# Usb_C_Hub-EasyEdaPro_Project.net
KiCad netlist of a schematic drawn in EasyEDA Pro
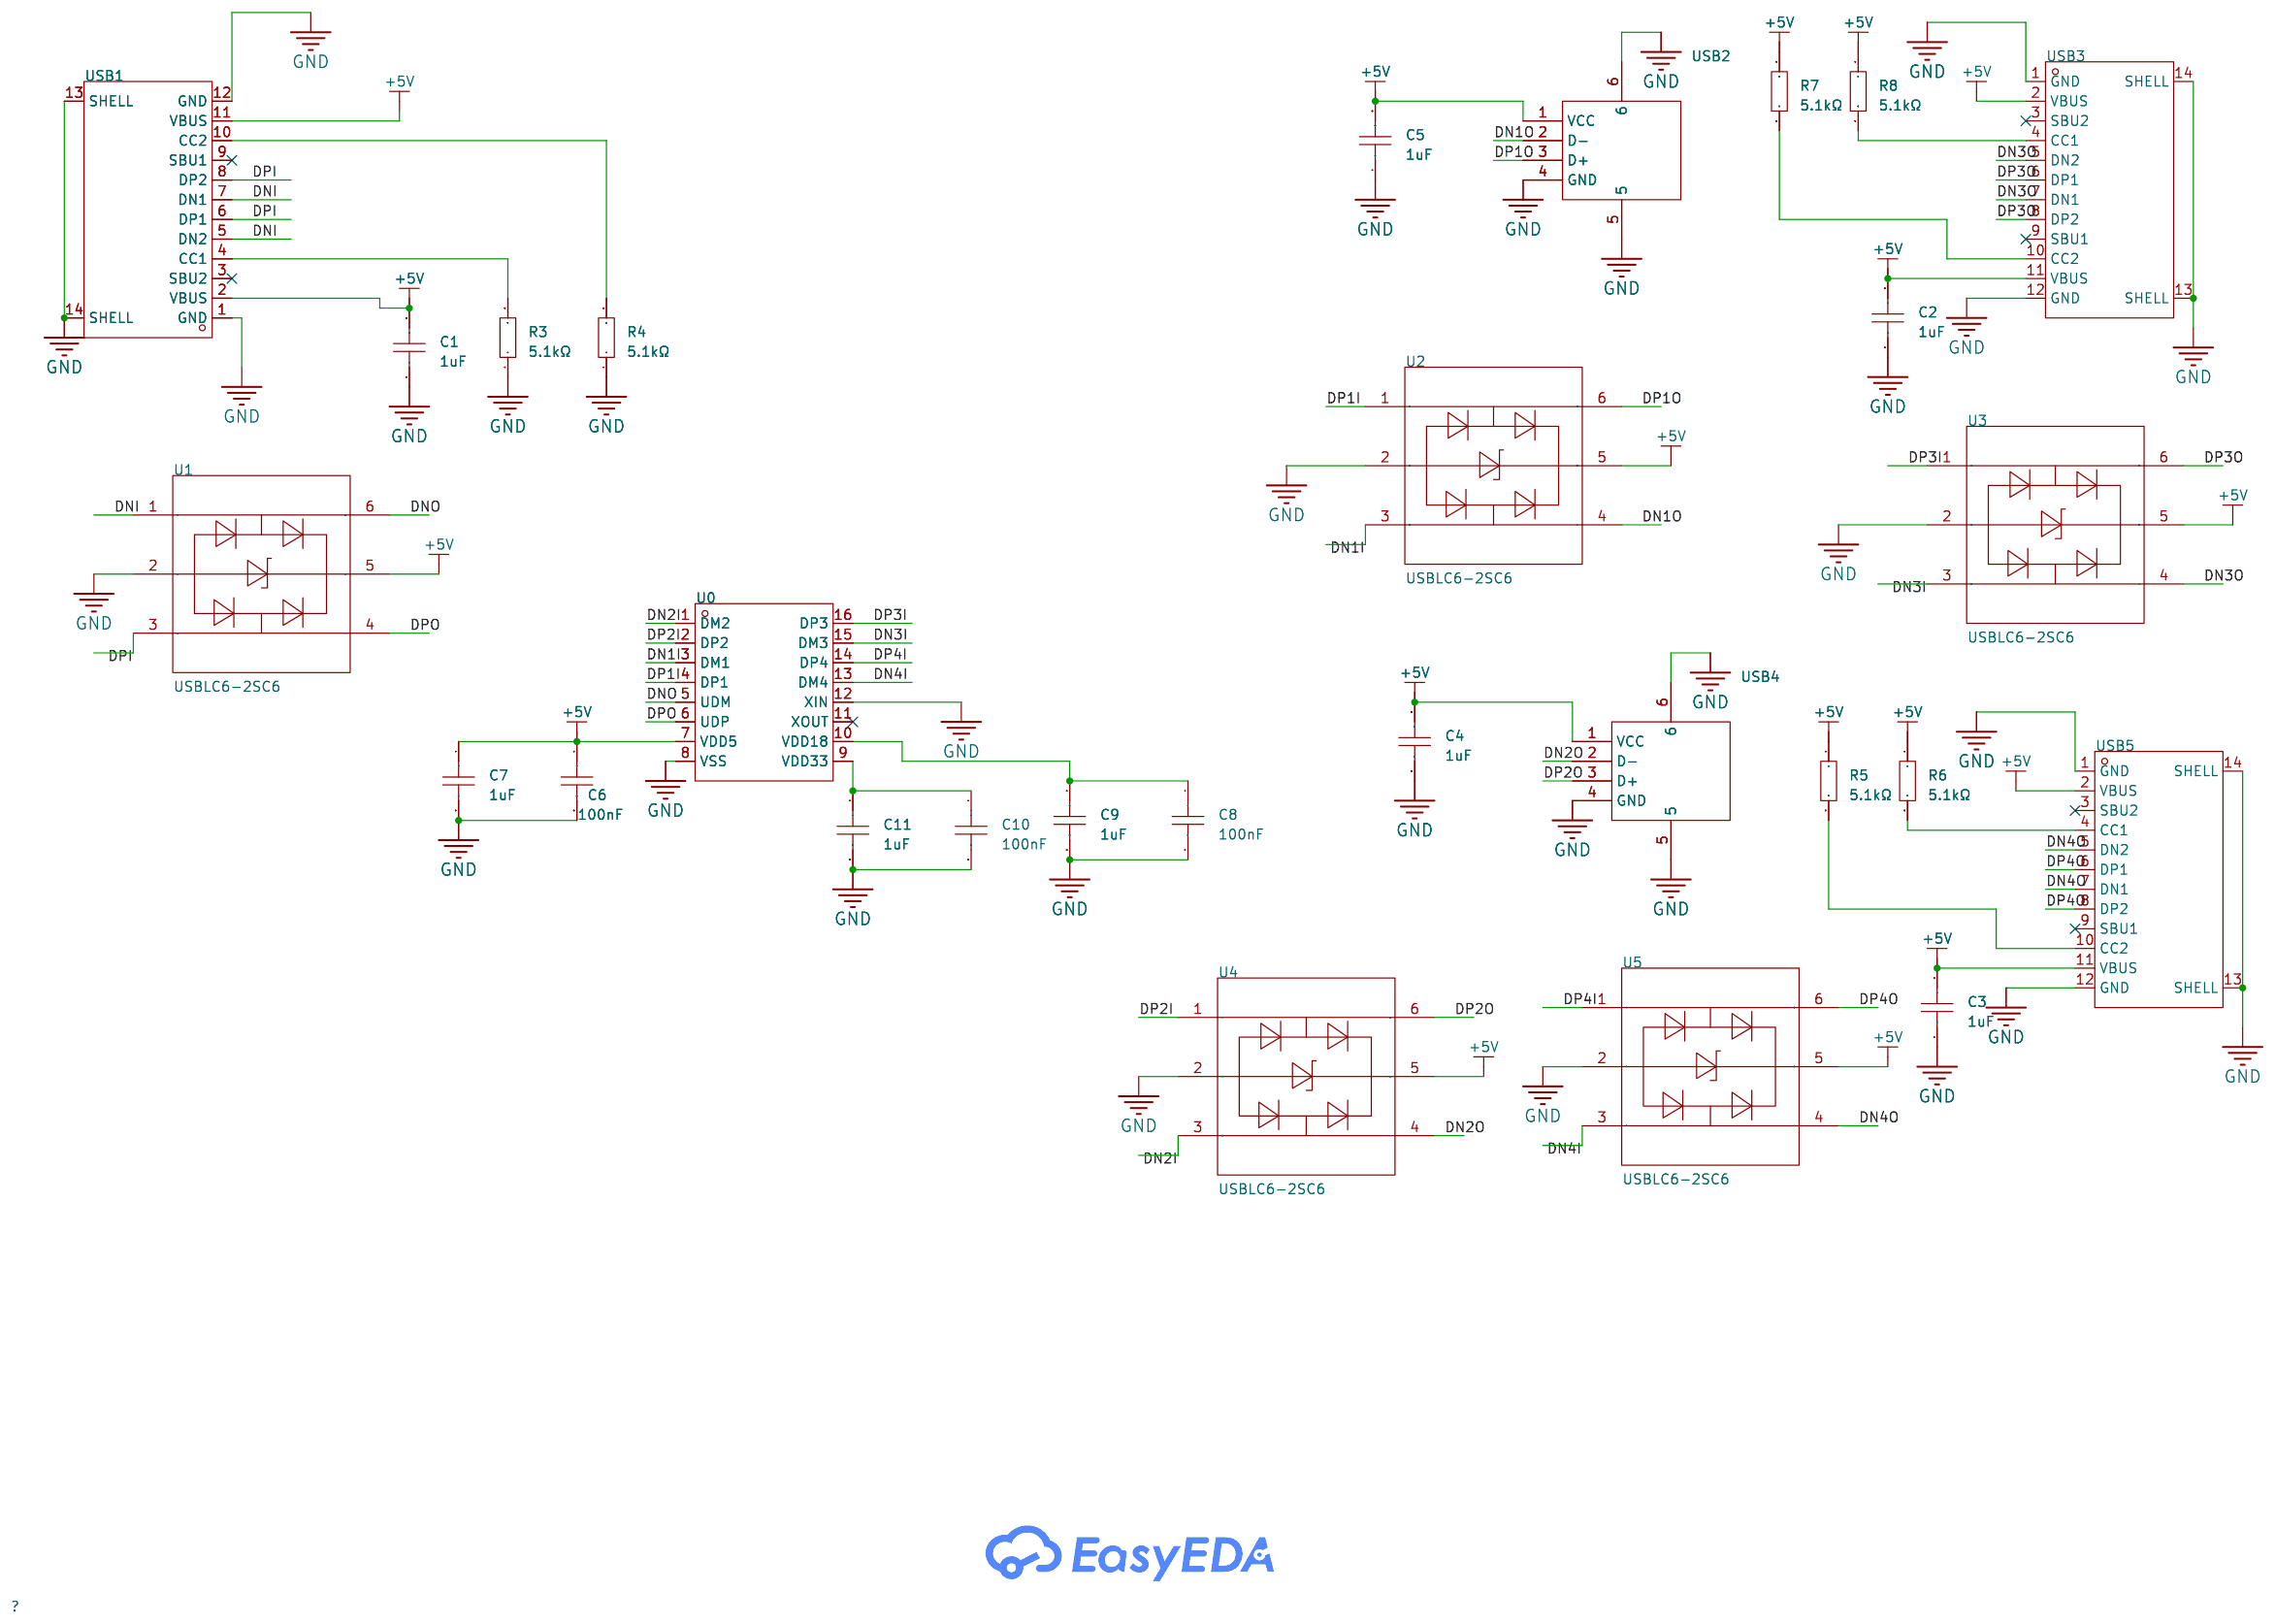
[diagram p0: schematic sheet]

(export (version "E")
  (design (tool "Eeschema 10.0.6"))
  (components
    (comp (ref "C1")
      (value "1uF")
      (footprint "easyedapro:C0603")
      (description "Capacitance:1uF Tolerance:±10% Tolerance:±10% Voltage Rating:50V Temperature Coefficient:X5R")
      (fields
        (field (name "Manufacturer Part") "CL10A105KB8NNNC")
        (field (name "Manufacturer") "SAMSUNG(三星)")
      )
      (libsource (lib "easyedapro") (part "CAP"))
    )
    (comp (ref "C2")
      (value "1uF")
      (footprint "easyedapro:C0603")
      (description "Capacitance:1uF Tolerance:±10% Tolerance:±10% Voltage Rating:50V Temperature Coefficient:X5R")
      (fields
        (field (name "Manufacturer Part") "CL10A105KB8NNNC")
        (field (name "Manufacturer") "SAMSUNG(三星)")
      )
      (libsource (lib "easyedapro") (part "CAP"))
    )
    (comp (ref "C3")
      (value "1uF")
      (footprint "easyedapro:C0603")
      (description "Capacitance:1uF Tolerance:±10% Tolerance:±10% Voltage Rating:50V Temperature Coefficient:X5R")
      (fields
        (field (name "Manufacturer Part") "CL10A105KB8NNNC")
        (field (name "Manufacturer") "SAMSUNG(三星)")
      )
      (libsource (lib "easyedapro") (part "CAP"))
    )
    (comp (ref "C4")
      (value "1uF")
      (footprint "easyedapro:C0603")
      (description "Capacitance:1uF Tolerance:±10% Tolerance:±10% Voltage Rating:50V Temperature Coefficient:X5R")
      (fields
        (field (name "Manufacturer Part") "CL10A105KB8NNNC")
        (field (name "Manufacturer") "SAMSUNG(三星)")
      )
      (libsource (lib "easyedapro") (part "CAP"))
    )
    (comp (ref "C5")
      (value "1uF")
      (footprint "easyedapro:C0603")
      (description "Capacitance:1uF Tolerance:±10% Tolerance:±10% Voltage Rating:50V Temperature Coefficient:X5R")
      (fields
        (field (name "Manufacturer Part") "CL10A105KB8NNNC")
        (field (name "Manufacturer") "SAMSUNG(三星)")
      )
      (libsource (lib "easyedapro") (part "CAP"))
    )
    (comp (ref "C6")
      (value "100nF")
      (footprint "easyedapro:C0603")
      (description "Capacitance:100nF Tolerance:±10% Tolerance:±10% Voltage Rating:50V Temperature Coefficient:X7R")
      (fields
        (field (name "Manufacturer Part") "CC0603KRX7R9BB104")
        (field (name "Manufacturer") "YAGEO(国巨)")
      )
      (libsource (lib "easyedapro") (part "CAP"))
    )
    (comp (ref "C7")
      (value "1uF")
      (footprint "easyedapro:C0603")
      (description "Capacitance:1uF Tolerance:±10% Tolerance:±10% Voltage Rating:50V Temperature Coefficient:X5R")
      (fields
        (field (name "Manufacturer Part") "CL10A105KB8NNNC")
        (field (name "Manufacturer") "SAMSUNG(三星)")
      )
      (libsource (lib "easyedapro") (part "CAP"))
    )
    (comp (ref "C8")
      (value "100nF")
      (footprint "easyedapro:C0603")
      (description "Capacitance:100nF Tolerance:±10% Tolerance:±10% Voltage Rating:50V Temperature Coefficient:X7R")
      (fields
        (field (name "Manufacturer Part") "CC0603KRX7R9BB104")
        (field (name "Manufacturer") "YAGEO(国巨)")
      )
      (libsource (lib "easyedapro") (part "CAP"))
    )
    (comp (ref "C9")
      (value "1uF")
      (footprint "easyedapro:C0603")
      (description "Capacitance:1uF Tolerance:±10% Tolerance:±10% Voltage Rating:50V Temperature Coefficient:X5R")
      (fields
        (field (name "Manufacturer Part") "CL10A105KB8NNNC")
        (field (name "Manufacturer") "SAMSUNG(三星)")
      )
      (libsource (lib "easyedapro") (part "CAP"))
    )
    (comp (ref "C10")
      (value "100nF")
      (footprint "easyedapro:C0603")
      (description "Capacitance:100nF Tolerance:±10% Tolerance:±10% Voltage Rating:50V Temperature Coefficient:X7R")
      (fields
        (field (name "Manufacturer Part") "CC0603KRX7R9BB104")
        (field (name "Manufacturer") "YAGEO(国巨)")
      )
      (libsource (lib "easyedapro") (part "CAP"))
    )
    (comp (ref "C11")
      (value "1uF")
      (footprint "easyedapro:C0603")
      (description "Capacitance:1uF Tolerance:±10% Tolerance:±10% Voltage Rating:50V Temperature Coefficient:X5R")
      (fields
        (field (name "Manufacturer Part") "CL10A105KB8NNNC")
        (field (name "Manufacturer") "SAMSUNG(三星)")
      )
      (libsource (lib "easyedapro") (part "CAP"))
    )
    (comp (ref "R3")
      (value "5.1kΩ")
      (footprint "easyedapro:R0603")
      (fields
        (field (name "Manufacturer Part") "0603WAF5101T5E")
        (field (name "Manufacturer") "UNI-ROYAL(厚声)")
      )
      (libsource (lib "easyedapro") (part "Res"))
    )
    (comp (ref "R4")
      (value "5.1kΩ")
      (footprint "easyedapro:R0603")
      (fields
        (field (name "Manufacturer Part") "0603WAF5101T5E")
        (field (name "Manufacturer") "UNI-ROYAL(厚声)")
      )
      (libsource (lib "easyedapro") (part "Res"))
    )
    (comp (ref "R5")
      (value "5.1kΩ")
      (footprint "easyedapro:R0603")
      (fields
        (field (name "Manufacturer Part") "0603WAF5101T5E")
        (field (name "Manufacturer") "UNI-ROYAL(厚声)")
      )
      (libsource (lib "easyedapro") (part "Res"))
    )
    (comp (ref "R6")
      (value "5.1kΩ")
      (footprint "easyedapro:R0603")
      (fields
        (field (name "Manufacturer Part") "0603WAF5101T5E")
        (field (name "Manufacturer") "UNI-ROYAL(厚声)")
      )
      (libsource (lib "easyedapro") (part "Res"))
    )
    (comp (ref "R7")
      (value "5.1kΩ")
      (footprint "easyedapro:R0603")
      (fields
        (field (name "Manufacturer Part") "0603WAF5101T5E")
        (field (name "Manufacturer") "UNI-ROYAL(厚声)")
      )
      (libsource (lib "easyedapro") (part "Res"))
    )
    (comp (ref "R8")
      (value "5.1kΩ")
      (footprint "easyedapro:R0603")
      (fields
        (field (name "Manufacturer Part") "0603WAF5101T5E")
        (field (name "Manufacturer") "UNI-ROYAL(厚声)")
      )
      (libsource (lib "easyedapro") (part "Res"))
    )
    (comp (ref "U0")
      (value "SL2.1s")
      (footprint "easyedapro:SSOP-16_L4.6-W2.6-P0.53-LS4.0-BL")
      (fields (field (name "Manufacturer") "CoreChips(和芯润德)"))
      (libsource (lib "easyedapro") (part "SL2.1S"))
    )
    (comp (ref "U1")
      (value "USBLC6-2SC6")
      (footprint "easyedapro:SOT-23-6_L2.9-W1.6-P0.95-LS2.8-BR")
      (fields (field (name "Manufacturer") "HXY MOSFET(华轩阳电子)"))
      (libsource (lib "easyedapro") (part "USBLC6-2SC6_C5261088"))
    )
    (comp (ref "U2")
      (value "USBLC6-2SC6")
      (footprint "easyedapro:SOT-23-6_L2.9-W1.6-P0.95-LS2.8-BR")
      (fields (field (name "Manufacturer") "HXY MOSFET(华轩阳电子)"))
      (libsource (lib "easyedapro") (part "USBLC6-2SC6_C5261088"))
    )
    (comp (ref "U3")
      (value "USBLC6-2SC6")
      (footprint "easyedapro:SOT-23-6_L2.9-W1.6-P0.95-LS2.8-BR")
      (fields (field (name "Manufacturer") "HXY MOSFET(华轩阳电子)"))
      (libsource (lib "easyedapro") (part "USBLC6-2SC6_C5261088"))
    )
    (comp (ref "U4")
      (value "USBLC6-2SC6")
      (footprint "easyedapro:SOT-23-6_L2.9-W1.6-P0.95-LS2.8-BR")
      (fields (field (name "Manufacturer") "HXY MOSFET(华轩阳电子)"))
      (libsource (lib "easyedapro") (part "USBLC6-2SC6_C5261088"))
    )
    (comp (ref "U5")
      (value "USBLC6-2SC6")
      (footprint "easyedapro:SOT-23-6_L2.9-W1.6-P0.95-LS2.8-BR")
      (fields (field (name "Manufacturer") "HXY MOSFET(华轩阳电子)"))
      (libsource (lib "easyedapro") (part "USBLC6-2SC6_C5261088"))
    )
    (comp (ref "USB1")
      (value "TYPE-C 16PIN 2MD(073)")
      (footprint "easyedapro:USB-C-SMD_TYPE-C-6PIN-2MD-073")
      (fields (field (name "Manufacturer") "SHOU HAN(首韩)"))
      (libsource (lib "easyedapro") (part "TYPE-C 16PIN 2MD(073)"))
    )
    (comp (ref "USB2")
      (value "10.0 QHHTZB6.3")
      (footprint "easyedapro:USB-A-TH_10.0QHHTZB6.3")
      (fields (field (name "Manufacturer") "SHOU HAN(首韩)"))
      (libsource (lib "easyedapro") (part "10.0 QHHTZB6.3"))
    )
    (comp (ref "USB3")
      (value "TYPE-C 16PIN 2MD(073)")
      (footprint "easyedapro:USB-C-SMD_TYPE-C-6PIN-2MD-073")
      (fields (field (name "Manufacturer") "SHOU HAN(首韩)"))
      (libsource (lib "easyedapro") (part "TYPE-C 16PIN 2MD(073)"))
    )
    (comp (ref "USB4")
      (value "10.0 QHHTZB6.3")
      (footprint "easyedapro:USB-A-TH_10.0QHHTZB6.3")
      (fields (field (name "Manufacturer") "SHOU HAN(首韩)"))
      (libsource (lib "easyedapro") (part "10.0 QHHTZB6.3"))
    )
    (comp (ref "USB5")
      (value "TYPE-C 16PIN 2MD(073)")
      (footprint "easyedapro:USB-C-SMD_TYPE-C-6PIN-2MD-073")
      (fields (field (name "Manufacturer") "SHOU HAN(首韩)"))
      (libsource (lib "easyedapro") (part "TYPE-C 16PIN 2MD(073)"))
    )
  )
  (nets
    (net (code "1") (name "+5V") (class "Default")
      (node (ref "C1") (pin "2") (pinfunction "2_2") (pintype "input"))
      (node (ref "C2") (pin "2") (pinfunction "2_2") (pintype "input"))
      (node (ref "C3") (pin "2") (pinfunction "2_2") (pintype "input"))
      (node (ref "C4") (pin "2") (pinfunction "2_2") (pintype "input"))
      (node (ref "C5") (pin "2") (pinfunction "2_2") (pintype "input"))
      (node (ref "C6") (pin "1") (pinfunction "1_1") (pintype "input"))
      (node (ref "C7") (pin "1") (pinfunction "1_1") (pintype "input"))
      (node (ref "R5") (pin "1") (pinfunction "1_1") (pintype "input"))
      (node (ref "R6") (pin "1") (pinfunction "1_1") (pintype "input"))
      (node (ref "R7") (pin "1") (pinfunction "1_1") (pintype "input"))
      (node (ref "R8") (pin "1") (pinfunction "1_1") (pintype "input"))
      (node (ref "U0") (pin "7") (pinfunction "VDD5_7") (pintype "unspecified"))
      (node (ref "U1") (pin "5") (pinfunction "5_5") (pintype "input"))
      (node (ref "U2") (pin "5") (pinfunction "5_5") (pintype "input"))
      (node (ref "U3") (pin "5") (pinfunction "5_5") (pintype "input"))
      (node (ref "U4") (pin "5") (pinfunction "5_5") (pintype "input"))
      (node (ref "U5") (pin "5") (pinfunction "5_5") (pintype "input"))
      (node (ref "USB1") (pin "11") (pinfunction "VBUS_11") (pintype "unspecified"))
      (node (ref "USB1") (pin "2") (pinfunction "VBUS_2") (pintype "unspecified"))
      (node (ref "USB2") (pin "1") (pinfunction "VCC_1") (pintype "unspecified"))
      (node (ref "USB3") (pin "11") (pinfunction "VBUS_11") (pintype "unspecified"))
      (node (ref "USB3") (pin "2") (pinfunction "VBUS_2") (pintype "unspecified"))
      (node (ref "USB4") (pin "1") (pinfunction "VCC_1") (pintype "unspecified"))
      (node (ref "USB5") (pin "11") (pinfunction "VBUS_11") (pintype "unspecified"))
      (node (ref "USB5") (pin "2") (pinfunction "VBUS_2") (pintype "unspecified"))
    )
    (net (code "2") (name "/DN1I") (class "Default")
      (node (ref "U0") (pin "3") (pinfunction "DM1_3") (pintype "unspecified"))
      (node (ref "U2") (pin "3") (pinfunction "3_3") (pintype "input"))
    )
    (net (code "3") (name "/DN1O") (class "Default")
      (node (ref "U2") (pin "4") (pinfunction "4_4") (pintype "input"))
      (node (ref "USB2") (pin "2") (pinfunction "D-_2") (pintype "unspecified"))
    )
    (net (code "4") (name "/DN2I") (class "Default")
      (node (ref "U0") (pin "1") (pinfunction "DM2_1") (pintype "unspecified"))
      (node (ref "U4") (pin "3") (pinfunction "3_3") (pintype "input"))
    )
    (net (code "5") (name "/DN2O") (class "Default")
      (node (ref "U4") (pin "4") (pinfunction "4_4") (pintype "input"))
      (node (ref "USB4") (pin "2") (pinfunction "D-_2") (pintype "unspecified"))
    )
    (net (code "6") (name "/DN3I") (class "Default")
      (node (ref "U0") (pin "15") (pinfunction "DM3_15") (pintype "unspecified"))
      (node (ref "U3") (pin "3") (pinfunction "3_3") (pintype "input"))
    )
    (net (code "7") (name "/DN3O") (class "Default")
      (node (ref "U3") (pin "4") (pinfunction "4_4") (pintype "input"))
      (node (ref "USB3") (pin "5") (pinfunction "DN2_5") (pintype "unspecified"))
      (node (ref "USB3") (pin "7") (pinfunction "DN1_7") (pintype "unspecified"))
    )
    (net (code "8") (name "/DN4I") (class "Default")
      (node (ref "U0") (pin "13") (pinfunction "DM4_13") (pintype "unspecified"))
      (node (ref "U5") (pin "3") (pinfunction "3_3") (pintype "input"))
    )
    (net (code "9") (name "/DN4O") (class "Default")
      (node (ref "U5") (pin "4") (pinfunction "4_4") (pintype "input"))
      (node (ref "USB5") (pin "5") (pinfunction "DN2_5") (pintype "unspecified"))
      (node (ref "USB5") (pin "7") (pinfunction "DN1_7") (pintype "unspecified"))
    )
    (net (code "10") (name "/DNI") (class "Default")
      (node (ref "U1") (pin "1") (pinfunction "1_1") (pintype "input"))
      (node (ref "USB1") (pin "5") (pinfunction "DN2_5") (pintype "unspecified"))
      (node (ref "USB1") (pin "7") (pinfunction "DN1_7") (pintype "unspecified"))
    )
    (net (code "11") (name "/DNO") (class "Default")
      (node (ref "U0") (pin "5") (pinfunction "UDM_5") (pintype "unspecified"))
      (node (ref "U1") (pin "6") (pinfunction "6_6") (pintype "input"))
    )
    (net (code "12") (name "/DP1I") (class "Default")
      (node (ref "U0") (pin "4") (pinfunction "DP1_4") (pintype "unspecified"))
      (node (ref "U2") (pin "1") (pinfunction "1_1") (pintype "input"))
    )
    (net (code "13") (name "/DP1O") (class "Default")
      (node (ref "U2") (pin "6") (pinfunction "6_6") (pintype "input"))
      (node (ref "USB2") (pin "3") (pinfunction "D+_3") (pintype "unspecified"))
    )
    (net (code "14") (name "/DP2I") (class "Default")
      (node (ref "U0") (pin "2") (pinfunction "DP2_2") (pintype "unspecified"))
      (node (ref "U4") (pin "1") (pinfunction "1_1") (pintype "input"))
    )
    (net (code "15") (name "/DP2O") (class "Default")
      (node (ref "U4") (pin "6") (pinfunction "6_6") (pintype "input"))
      (node (ref "USB4") (pin "3") (pinfunction "D+_3") (pintype "unspecified"))
    )
    (net (code "16") (name "/DP3I") (class "Default")
      (node (ref "U0") (pin "16") (pinfunction "DP3_16") (pintype "unspecified"))
      (node (ref "U3") (pin "1") (pinfunction "1_1") (pintype "input"))
    )
    (net (code "17") (name "/DP3O") (class "Default")
      (node (ref "U3") (pin "6") (pinfunction "6_6") (pintype "input"))
      (node (ref "USB3") (pin "6") (pinfunction "DP1_6") (pintype "unspecified"))
      (node (ref "USB3") (pin "8") (pinfunction "DP2_8") (pintype "unspecified"))
    )
    (net (code "18") (name "/DP4I") (class "Default")
      (node (ref "U0") (pin "14") (pinfunction "DP4_14") (pintype "unspecified"))
      (node (ref "U5") (pin "1") (pinfunction "1_1") (pintype "input"))
    )
    (net (code "19") (name "/DP4O") (class "Default")
      (node (ref "U5") (pin "6") (pinfunction "6_6") (pintype "input"))
      (node (ref "USB5") (pin "6") (pinfunction "DP1_6") (pintype "unspecified"))
      (node (ref "USB5") (pin "8") (pinfunction "DP2_8") (pintype "unspecified"))
    )
    (net (code "20") (name "/DPI") (class "Default")
      (node (ref "U1") (pin "3") (pinfunction "3_3") (pintype "input"))
      (node (ref "USB1") (pin "6") (pinfunction "DP1_6") (pintype "unspecified"))
      (node (ref "USB1") (pin "8") (pinfunction "DP2_8") (pintype "unspecified"))
    )
    (net (code "21") (name "/DPO") (class "Default")
      (node (ref "U0") (pin "6") (pinfunction "UDP_6") (pintype "unspecified"))
      (node (ref "U1") (pin "4") (pinfunction "4_4") (pintype "input"))
    )
    (net (code "22") (name "GND") (class "Default")
      (node (ref "C1") (pin "1") (pinfunction "1_1") (pintype "input"))
      (node (ref "C10") (pin "2") (pinfunction "2_2") (pintype "input"))
      (node (ref "C11") (pin "2") (pinfunction "2_2") (pintype "input"))
      (node (ref "C2") (pin "1") (pinfunction "1_1") (pintype "input"))
      (node (ref "C3") (pin "1") (pinfunction "1_1") (pintype "input"))
      (node (ref "C4") (pin "1") (pinfunction "1_1") (pintype "input"))
      (node (ref "C5") (pin "1") (pinfunction "1_1") (pintype "input"))
      (node (ref "C6") (pin "2") (pinfunction "2_2") (pintype "input"))
      (node (ref "C7") (pin "2") (pinfunction "2_2") (pintype "input"))
      (node (ref "C8") (pin "2") (pinfunction "2_2") (pintype "input"))
      (node (ref "C9") (pin "2") (pinfunction "2_2") (pintype "input"))
      (node (ref "R3") (pin "1") (pinfunction "1_1") (pintype "input"))
      (node (ref "R4") (pin "1") (pinfunction "1_1") (pintype "input"))
      (node (ref "U0") (pin "12") (pinfunction "XIN_12") (pintype "unspecified"))
      (node (ref "U0") (pin "8") (pinfunction "VSS_8") (pintype "unspecified"))
      (node (ref "U1") (pin "2") (pinfunction "2_2") (pintype "input"))
      (node (ref "U2") (pin "2") (pinfunction "2_2") (pintype "input"))
      (node (ref "U3") (pin "2") (pinfunction "2_2") (pintype "input"))
      (node (ref "U4") (pin "2") (pinfunction "2_2") (pintype "input"))
      (node (ref "U5") (pin "2") (pinfunction "2_2") (pintype "input"))
      (node (ref "USB1") (pin "1") (pinfunction "GND_1") (pintype "unspecified"))
      (node (ref "USB1") (pin "12") (pinfunction "GND_12") (pintype "unspecified"))
      (node (ref "USB1") (pin "13") (pinfunction "SHELL_13") (pintype "unspecified"))
      (node (ref "USB1") (pin "14") (pinfunction "SHELL_14") (pintype "unspecified"))
      (node (ref "USB2") (pin "4") (pinfunction "GND_4") (pintype "unspecified"))
      (node (ref "USB2") (pin "5") (pinfunction "5_5") (pintype "unspecified"))
      (node (ref "USB2") (pin "6") (pinfunction "6_6") (pintype "unspecified"))
      (node (ref "USB3") (pin "1") (pinfunction "GND_1") (pintype "unspecified"))
      (node (ref "USB3") (pin "12") (pinfunction "GND_12") (pintype "unspecified"))
      (node (ref "USB3") (pin "13") (pinfunction "SHELL_13") (pintype "unspecified"))
      (node (ref "USB3") (pin "14") (pinfunction "SHELL_14") (pintype "unspecified"))
      (node (ref "USB4") (pin "4") (pinfunction "GND_4") (pintype "unspecified"))
      (node (ref "USB4") (pin "5") (pinfunction "5_5") (pintype "unspecified"))
      (node (ref "USB4") (pin "6") (pinfunction "6_6") (pintype "unspecified"))
      (node (ref "USB5") (pin "1") (pinfunction "GND_1") (pintype "unspecified"))
      (node (ref "USB5") (pin "12") (pinfunction "GND_12") (pintype "unspecified"))
      (node (ref "USB5") (pin "13") (pinfunction "SHELL_13") (pintype "unspecified"))
      (node (ref "USB5") (pin "14") (pinfunction "SHELL_14") (pintype "unspecified"))
    )
    (net (code "23") (name "Net-(U0-VDD18)") (class "Default")
      (node (ref "C8") (pin "1") (pinfunction "1_1") (pintype "input"))
      (node (ref "C9") (pin "1") (pinfunction "1_1") (pintype "input"))
      (node (ref "U0") (pin "10") (pinfunction "VDD18_10") (pintype "unspecified"))
    )
    (net (code "24") (name "Net-(U0-VDD33)") (class "Default")
      (node (ref "C10") (pin "1") (pinfunction "1_1") (pintype "input"))
      (node (ref "C11") (pin "1") (pinfunction "1_1") (pintype "input"))
      (node (ref "U0") (pin "9") (pinfunction "VDD33_9") (pintype "unspecified"))
    )
    (net (code "25") (name "Net-(USB1-CC1)") (class "Default")
      (node (ref "R3") (pin "2") (pinfunction "2_2") (pintype "input"))
      (node (ref "USB1") (pin "4") (pinfunction "CC1_4") (pintype "unspecified"))
    )
    (net (code "26") (name "Net-(USB1-CC2)") (class "Default")
      (node (ref "R4") (pin "2") (pinfunction "2_2") (pintype "input"))
      (node (ref "USB1") (pin "10") (pinfunction "CC2_10") (pintype "unspecified"))
    )
    (net (code "27") (name "Net-(USB3-CC1)") (class "Default")
      (node (ref "R8") (pin "2") (pinfunction "2_2") (pintype "input"))
      (node (ref "USB3") (pin "4") (pinfunction "CC1_4") (pintype "unspecified"))
    )
    (net (code "28") (name "Net-(USB3-CC2)") (class "Default")
      (node (ref "R7") (pin "2") (pinfunction "2_2") (pintype "input"))
      (node (ref "USB3") (pin "10") (pinfunction "CC2_10") (pintype "unspecified"))
    )
    (net (code "29") (name "Net-(USB5-CC1)") (class "Default")
      (node (ref "R6") (pin "2") (pinfunction "2_2") (pintype "input"))
      (node (ref "USB5") (pin "4") (pinfunction "CC1_4") (pintype "unspecified"))
    )
    (net (code "30") (name "Net-(USB5-CC2)") (class "Default")
      (node (ref "R5") (pin "2") (pinfunction "2_2") (pintype "input"))
      (node (ref "USB5") (pin "10") (pinfunction "CC2_10") (pintype "unspecified"))
    )
    (net (code "31") (name "unconnected-(U0-XOUT-Pad11)") (class "Default")
      (node (ref "U0") (pin "11") (pinfunction "XOUT_11") (pintype "unspecified+no_connect"))
    )
    (net (code "32") (name "unconnected-(USB1-SBU1-Pad9)") (class "Default")
      (node (ref "USB1") (pin "9") (pinfunction "SBU1_9") (pintype "unspecified+no_connect"))
    )
    (net (code "33") (name "unconnected-(USB1-SBU2-Pad3)") (class "Default")
      (node (ref "USB1") (pin "3") (pinfunction "SBU2_3") (pintype "unspecified+no_connect"))
    )
    (net (code "34") (name "unconnected-(USB3-SBU1-Pad9)") (class "Default")
      (node (ref "USB3") (pin "9") (pinfunction "SBU1_9") (pintype "unspecified+no_connect"))
    )
    (net (code "35") (name "unconnected-(USB3-SBU2-Pad3)") (class "Default")
      (node (ref "USB3") (pin "3") (pinfunction "SBU2_3") (pintype "unspecified+no_connect"))
    )
    (net (code "36") (name "unconnected-(USB5-SBU1-Pad9)") (class "Default")
      (node (ref "USB5") (pin "9") (pinfunction "SBU1_9") (pintype "unspecified+no_connect"))
    )
    (net (code "37") (name "unconnected-(USB5-SBU2-Pad3)") (class "Default")
      (node (ref "USB5") (pin "3") (pinfunction "SBU2_3") (pintype "unspecified+no_connect"))
    )
  )
)
